# gyro.net
KiCad netlist of a schematic drawn in EAGLE
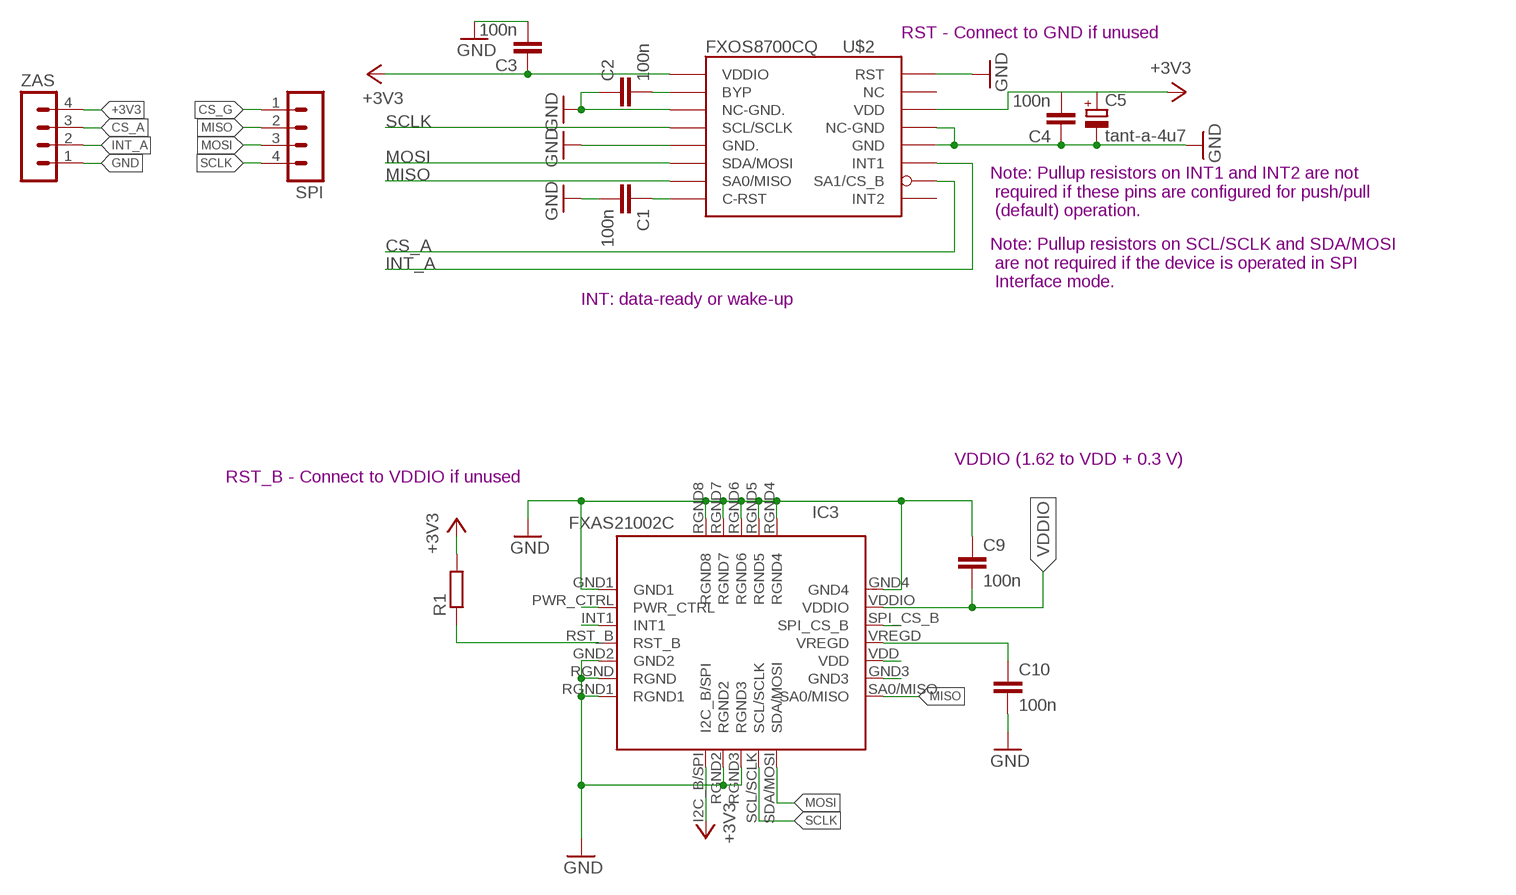
[diagram p0: schematic, sheet 1]

(export (version "E")
  (design (tool "Eeschema 10.0.6"))
  (components
    (comp (ref "C1")
      (value "100n")
      (footprint "eagle-import:C0603")
      (libsource (lib "eagle-import") (part "C-EUC0603"))
    )
    (comp (ref "C2")
      (value "100n")
      (footprint "eagle-import:C0603")
      (libsource (lib "eagle-import") (part "C-EUC0603"))
    )
    (comp (ref "C3")
      (value "100n")
      (footprint "eagle-import:C0603")
      (libsource (lib "eagle-import") (part "C-EUC0603"))
    )
    (comp (ref "C4")
      (value "100n")
      (footprint "eagle-import:C0603")
      (libsource (lib "eagle-import") (part "C-EUC0603"))
    )
    (comp (ref "C5")
      (value "tant-a-4u7")
      (footprint "eagle-import:SMC_A")
      (libsource (lib "eagle-import") (part "CPOL-EUSMCA"))
    )
    (comp (ref "C9")
      (value "100n")
      (footprint "eagle-import:C0603")
      (libsource (lib "eagle-import") (part "C-EUC0603"))
    )
    (comp (ref "C10")
      (value "100n")
      (footprint "eagle-import:C0603")
      (libsource (lib "eagle-import") (part "C-EUC0603"))
    )
    (comp (ref "IC3")
      (value "FXAS21002C")
      (footprint "eagle-import:QFN24-4X4")
      (libsource (lib "eagle-import") (part "FXAS21002C"))
    )
    (comp (ref "R1")
      (value "R-EU_R0603")
      (footprint "eagle-import:R0603")
      (libsource (lib "eagle-import") (part "R-EU_R0603"))
    )
    (comp (ref "SPI")
      (value "MA04-1")
      (footprint "eagle-import:MA04-1")
      (libsource (lib "eagle-import") (part "MA04-1"))
    )
    (comp (ref "U$2")
      (value "FXOS8700CQR1")
      (footprint "eagle-import:QFN16-5X3")
      (libsource (lib "eagle-import") (part "FXOS8700CQR1"))
    )
    (comp (ref "ZAS")
      (value "MA04-1")
      (footprint "eagle-import:MA04-1")
      (libsource (lib "eagle-import") (part "MA04-1"))
    )
  )
  (nets
    (net (code "1") (name "+3V3") (class "Default")
      (node (ref "C3") (pin "1") (pinfunction "1_1") (pintype "passive"))
      (node (ref "C4") (pin "2") (pinfunction "2_2") (pintype "passive"))
      (node (ref "C5") (pin "+") (pinfunction "+_+") (pintype "passive"))
      (node (ref "IC3") (pin "I2C_B/SPI") (pinfunction "I2C_B/SPI_I2C_B/SPI") (pintype "bidirectional"))
      (node (ref "IC3") (pin "VDD") (pinfunction "VDD_VDD") (pintype "bidirectional"))
      (node (ref "R1") (pin "2") (pinfunction "2_2") (pintype "passive"))
      (node (ref "U$2") (pin "P$1") (pinfunction "VDDIO_P$1") (pintype "power_in"))
      (node (ref "U$2") (pin "P$14") (pinfunction "VDD_P$14") (pintype "power_in"))
      (node (ref "ZAS") (pin "4") (pinfunction "4_4") (pintype "passive"))
    )
    (net (code "2") (name "CS_A") (class "Default")
      (node (ref "U$2") (pin "P$10") (pinfunction "SA1/CS_B_P$10") (pintype "input"))
      (node (ref "ZAS") (pin "3") (pinfunction "3_3") (pintype "passive"))
    )
    (net (code "3") (name "CS_G") (class "Default")
      (node (ref "IC3") (pin "SPI_CS_B") (pinfunction "SPI_CS_B_SPI_CS_B") (pintype "bidirectional"))
      (node (ref "SPI") (pin "1") (pinfunction "1_1") (pintype "passive"))
    )
    (net (code "4") (name "GND") (class "Default")
      (node (ref "C1") (pin "2") (pinfunction "2_2") (pintype "passive"))
      (node (ref "C10") (pin "2") (pinfunction "2_2") (pintype "passive"))
      (node (ref "C2") (pin "1") (pinfunction "1_1") (pintype "passive"))
      (node (ref "C3") (pin "2") (pinfunction "2_2") (pintype "passive"))
      (node (ref "C4") (pin "1") (pinfunction "1_1") (pintype "passive"))
      (node (ref "C5") (pin "-") (pinfunction "-_-") (pintype "passive"))
      (node (ref "C9") (pin "1") (pinfunction "1_1") (pintype "passive"))
      (node (ref "IC3") (pin "GND1") (pinfunction "GND1_GND1") (pintype "bidirectional"))
      (node (ref "IC3") (pin "GND2") (pinfunction "GND2_GND2") (pintype "bidirectional"))
      (node (ref "IC3") (pin "GND3") (pinfunction "GND3_GND3") (pintype "bidirectional"))
      (node (ref "IC3") (pin "GND4") (pinfunction "GND4_GND4") (pintype "bidirectional"))
      (node (ref "IC3") (pin "RGND") (pinfunction "RGND_RGND") (pintype "bidirectional"))
      (node (ref "IC3") (pin "RGND1") (pinfunction "RGND1_RGND1") (pintype "bidirectional"))
      (node (ref "IC3") (pin "RGND2") (pinfunction "RGND2_RGND2") (pintype "bidirectional"))
      (node (ref "IC3") (pin "RGND3") (pinfunction "RGND3_RGND3") (pintype "bidirectional"))
      (node (ref "IC3") (pin "RGND4") (pinfunction "RGND4_RGND4") (pintype "bidirectional"))
      (node (ref "IC3") (pin "RGND5") (pinfunction "RGND5_RGND5") (pintype "bidirectional"))
      (node (ref "IC3") (pin "RGND6") (pinfunction "RGND6_RGND6") (pintype "bidirectional"))
      (node (ref "IC3") (pin "RGND7") (pinfunction "RGND7_RGND7") (pintype "bidirectional"))
      (node (ref "IC3") (pin "RGND8") (pinfunction "RGND8_RGND8") (pintype "bidirectional"))
      (node (ref "U$2") (pin "P$12") (pinfunction "GND_P$12") (pintype "power_in"))
      (node (ref "U$2") (pin "P$13") (pinfunction "NC-GND_P$13") (pintype "input"))
      (node (ref "U$2") (pin "P$16") (pinfunction "RST_P$16") (pintype "input"))
      (node (ref "U$2") (pin "P$3") (pinfunction "NC-GND._P$3") (pintype "input"))
      (node (ref "U$2") (pin "P$5") (pinfunction "GND._P$5") (pintype "power_in"))
      (node (ref "ZAS") (pin "1") (pinfunction "1_1") (pintype "passive"))
    )
    (net (code "5") (name "INT_A") (class "Default")
      (node (ref "U$2") (pin "P$11") (pinfunction "INT1_P$11") (pintype "output"))
      (node (ref "ZAS") (pin "2") (pinfunction "2_2") (pintype "passive"))
    )
    (net (code "6") (name "MISO") (class "Default")
      (node (ref "IC3") (pin "SA0/MISO") (pinfunction "SA0/MISO_SA0/MISO") (pintype "bidirectional"))
      (node (ref "SPI") (pin "2") (pinfunction "2_2") (pintype "passive"))
      (node (ref "U$2") (pin "P$7") (pinfunction "SA0/MISO_P$7") (pintype "output"))
    )
    (net (code "7") (name "MOSI") (class "Default")
      (node (ref "IC3") (pin "SDA/MOSI") (pinfunction "SDA/MOSI_SDA/MOSI") (pintype "bidirectional"))
      (node (ref "SPI") (pin "3") (pinfunction "3_3") (pintype "passive"))
      (node (ref "U$2") (pin "P$6") (pinfunction "SDA/MOSI_P$6") (pintype "input"))
    )
    (net (code "8") (name "Net-(C10-Pad1)") (class "Default")
      (node (ref "C10") (pin "1") (pinfunction "1_1") (pintype "passive"))
      (node (ref "IC3") (pin "VREGD") (pinfunction "VREGD_VREGD") (pintype "bidirectional"))
    )
    (net (code "9") (name "Net-(IC3-PadRST_B)") (class "Default")
      (node (ref "IC3") (pin "RST_B") (pinfunction "RST_B_RST_B") (pintype "bidirectional"))
      (node (ref "R1") (pin "1") (pinfunction "1_1") (pintype "passive"))
    )
    (net (code "10") (name "Net-(U$2-BYP)") (class "Default")
      (node (ref "C2") (pin "2") (pinfunction "2_2") (pintype "passive"))
      (node (ref "U$2") (pin "P$2") (pinfunction "BYP_P$2") (pintype "bidirectional"))
    )
    (net (code "11") (name "Net-(U$2-C-RST)") (class "Default")
      (node (ref "C1") (pin "1") (pinfunction "1_1") (pintype "passive"))
      (node (ref "U$2") (pin "P$8") (pinfunction "C-RST_P$8") (pintype "bidirectional"))
    )
    (net (code "12") (name "SCLK") (class "Default")
      (node (ref "IC3") (pin "SCL/SCLK") (pinfunction "SCL/SCLK_SCL/SCLK") (pintype "bidirectional"))
      (node (ref "SPI") (pin "4") (pinfunction "4_4") (pintype "passive"))
      (node (ref "U$2") (pin "P$4") (pinfunction "SCL/SCLK_P$4") (pintype "input"))
    )
    (net (code "13") (name "VDDIO") (class "Default")
      (node (ref "C9") (pin "2") (pinfunction "2_2") (pintype "passive"))
      (node (ref "IC3") (pin "VDDIO") (pinfunction "VDDIO_VDDIO") (pintype "bidirectional"))
    )
    (net (code "14") (name "unconnected-(IC3-PadINT1)") (class "Default")
      (node (ref "IC3") (pin "INT1") (pinfunction "INT1_INT1") (pintype "bidirectional"))
    )
    (net (code "15") (name "unconnected-(IC3-PadPWR_CTRL)") (class "Default")
      (node (ref "IC3") (pin "PWR_CTRL") (pinfunction "PWR_CTRL_PWR_CTRL") (pintype "bidirectional"))
    )
    (net (code "16") (name "unconnected-(U$2-INT2-PadP$9)") (class "Default")
      (node (ref "U$2") (pin "P$9") (pinfunction "INT2_P$9") (pintype "output"))
    )
    (net (code "17") (name "unconnected-(U$2-NC-PadP$15)") (class "Default")
      (node (ref "U$2") (pin "P$15") (pinfunction "NC_P$15") (pintype "no_connect"))
    )
  )
)
